# xspi_v4.net
KiCad netlist of a schematic drawn in EAGLE
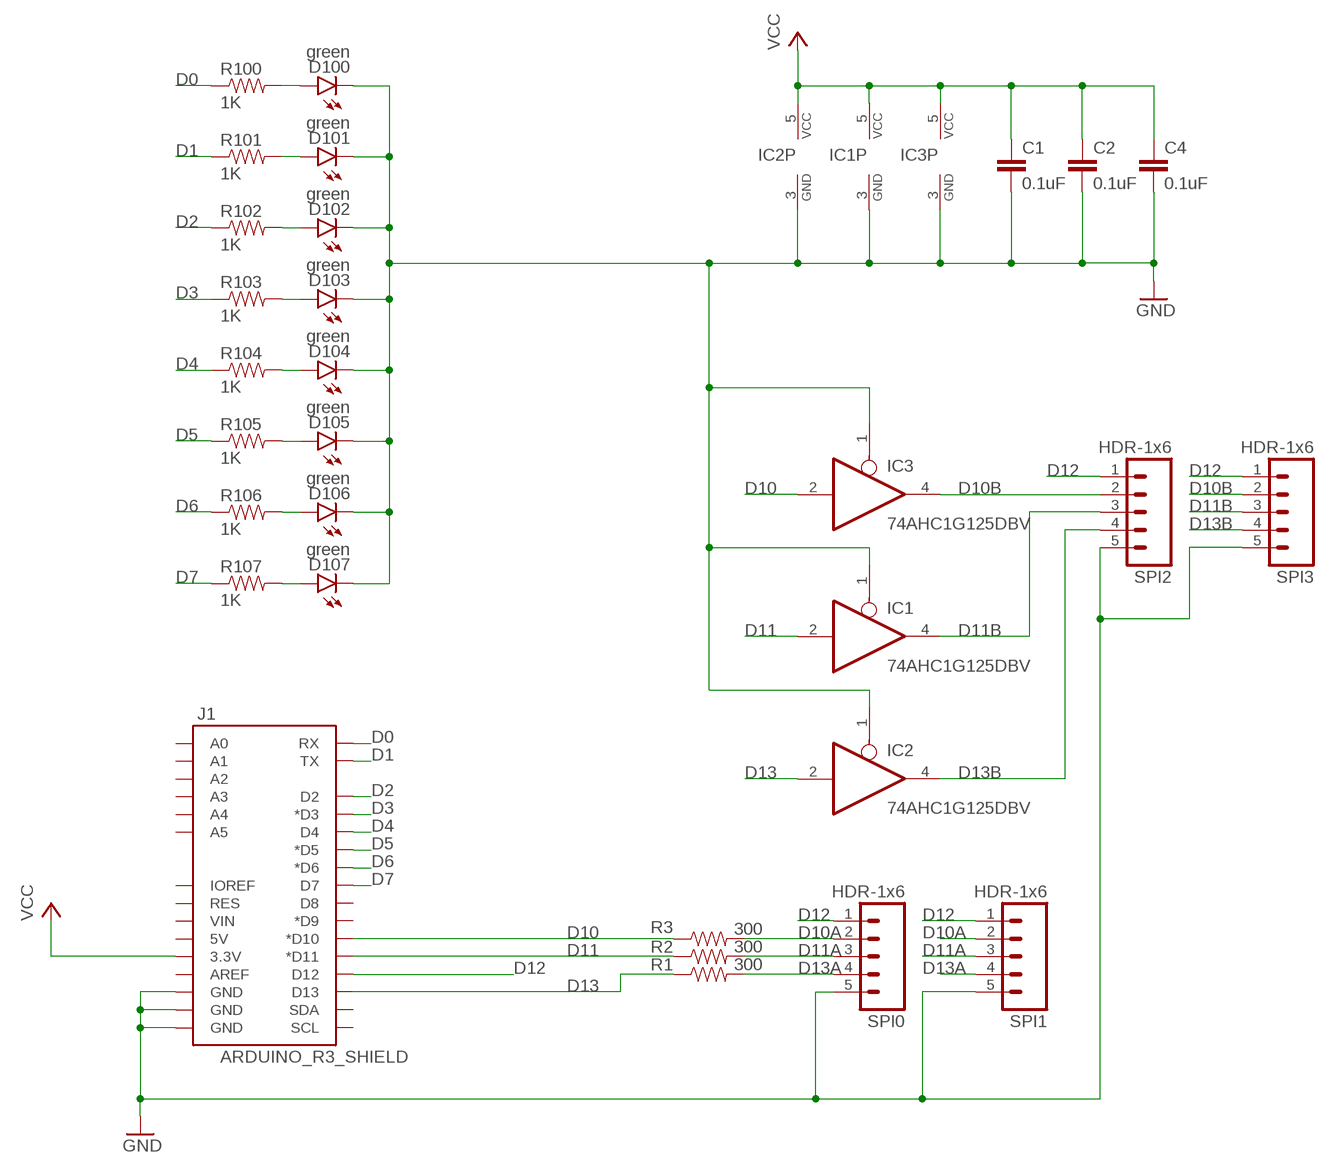
[diagram p0: schematic, sheet 1]

(export (version "E")
  (design (tool "Eeschema 10.0.6"))
  (components
    (comp (ref "C1")
      (value "0.1uF")
      (footprint "eagle-import:0805-CAP")
      (fields (field (name "PROD_ID") "0805"))
      (libsource (lib "eagle-import") (part "1.0UF-25V-+80/-20(0805){dblquote}"))
    )
    (comp (ref "C2")
      (value "0.1uF")
      (footprint "eagle-import:0805-CAP")
      (fields (field (name "PROD_ID") "0805"))
      (libsource (lib "eagle-import") (part "1.0UF-25V-+80/-20(0805){dblquote}"))
    )
    (comp (ref "C4")
      (value "0.1uF")
      (footprint "eagle-import:0805-CAP")
      (fields (field (name "PROD_ID") "0805"))
      (libsource (lib "eagle-import") (part "1.0UF-25V-+80/-20(0805){dblquote}"))
    )
    (comp (ref "D100")
      (value "green")
      (footprint "eagle-import:FKIT-LED-1206")
      (libsource (lib "eagle-import") (part "LED-FKIT-1206"))
    )
    (comp (ref "D101")
      (value "green")
      (footprint "eagle-import:FKIT-LED-1206")
      (libsource (lib "eagle-import") (part "LED-FKIT-1206"))
    )
    (comp (ref "D102")
      (value "green")
      (footprint "eagle-import:FKIT-LED-1206")
      (libsource (lib "eagle-import") (part "LED-FKIT-1206"))
    )
    (comp (ref "D103")
      (value "green")
      (footprint "eagle-import:FKIT-LED-1206")
      (libsource (lib "eagle-import") (part "LED-FKIT-1206"))
    )
    (comp (ref "D104")
      (value "green")
      (footprint "eagle-import:FKIT-LED-1206")
      (libsource (lib "eagle-import") (part "LED-FKIT-1206"))
    )
    (comp (ref "D105")
      (value "green")
      (footprint "eagle-import:FKIT-LED-1206")
      (libsource (lib "eagle-import") (part "LED-FKIT-1206"))
    )
    (comp (ref "D106")
      (value "green")
      (footprint "eagle-import:FKIT-LED-1206")
      (libsource (lib "eagle-import") (part "LED-FKIT-1206"))
    )
    (comp (ref "D107")
      (value "green")
      (footprint "eagle-import:FKIT-LED-1206")
      (libsource (lib "eagle-import") (part "LED-FKIT-1206"))
    )
    (comp (ref "IC1")
      (value "74AHC1G125DBV")
      (footprint "eagle-import:SOT23-5")
      (libsource (lib "eagle-import") (part "741G125DBVAHC"))
    )
    (comp (ref "IC2")
      (value "74AHC1G125DBV")
      (footprint "eagle-import:SOT23-5")
      (libsource (lib "eagle-import") (part "741G125DBVAHC"))
    )
    (comp (ref "IC3")
      (value "74AHC1G125DBV")
      (footprint "eagle-import:SOT23-5")
      (libsource (lib "eagle-import") (part "741G125DBVAHC"))
    )
    (comp (ref "J1")
      (value "ARDUINO_R3_SHIELD")
      (footprint "eagle-import:UNO_R3_SHIELD")
      (libsource (lib "eagle-import") (part "ARDUINO_R3_SHIELD"))
    )
    (comp (ref "R1")
      (value "300")
      (footprint "eagle-import:AXIAL-0.4")
      (libsource (lib "eagle-import") (part "RESISTORPTH-1/4W"))
    )
    (comp (ref "R2")
      (value "300")
      (footprint "eagle-import:AXIAL-0.4")
      (libsource (lib "eagle-import") (part "RESISTORPTH-1/4W"))
    )
    (comp (ref "R3")
      (value "300")
      (footprint "eagle-import:AXIAL-0.4")
      (libsource (lib "eagle-import") (part "RESISTORPTH-1/4W"))
    )
    (comp (ref "R100")
      (value "1K")
      (footprint "eagle-import:0805")
      (libsource (lib "eagle-import") (part "RESISTOR0805-RES"))
    )
    (comp (ref "R101")
      (value "1K")
      (footprint "eagle-import:0805")
      (libsource (lib "eagle-import") (part "RESISTOR0805-RES"))
    )
    (comp (ref "R102")
      (value "1K")
      (footprint "eagle-import:0805")
      (libsource (lib "eagle-import") (part "RESISTOR0805-RES"))
    )
    (comp (ref "R103")
      (value "1K")
      (footprint "eagle-import:0805")
      (libsource (lib "eagle-import") (part "RESISTOR0805-RES"))
    )
    (comp (ref "R104")
      (value "1K")
      (footprint "eagle-import:0805")
      (libsource (lib "eagle-import") (part "RESISTOR0805-RES"))
    )
    (comp (ref "R105")
      (value "1K")
      (footprint "eagle-import:0805")
      (libsource (lib "eagle-import") (part "RESISTOR0805-RES"))
    )
    (comp (ref "R106")
      (value "1K")
      (footprint "eagle-import:0805")
      (libsource (lib "eagle-import") (part "RESISTOR0805-RES"))
    )
    (comp (ref "R107")
      (value "1K")
      (footprint "eagle-import:0805")
      (libsource (lib "eagle-import") (part "RESISTOR0805-RES"))
    )
    (comp (ref "SPI0")
      (value "HDR-1x6")
      (footprint "eagle-import:1X05_LONGPADS")
      (libsource (lib "eagle-import") (part "M05PTH_LONGPADS"))
    )
    (comp (ref "SPI1")
      (value "HDR-1x6")
      (footprint "eagle-import:1X05_LONGPADS")
      (libsource (lib "eagle-import") (part "M05PTH_LONGPADS"))
    )
    (comp (ref "SPI2")
      (value "HDR-1x6")
      (footprint "eagle-import:1X05_LONGPADS")
      (libsource (lib "eagle-import") (part "M05PTH_LONGPADS"))
    )
    (comp (ref "SPI3")
      (value "HDR-1x6")
      (footprint "eagle-import:1X05_LONGPADS")
      (libsource (lib "eagle-import") (part "M05PTH_LONGPADS"))
    )
  )
  (nets
    (net (code "1") (name "/D0") (class "Default")
      (node (ref "J1") (pin "RX") (pinfunction "RX_RX") (pintype "bidirectional"))
      (node (ref "R100") (pin "1") (pinfunction "1_1") (pintype "passive"))
    )
    (net (code "2") (name "/D1") (class "Default")
      (node (ref "J1") (pin "TX") (pinfunction "TX_TX") (pintype "bidirectional"))
      (node (ref "R101") (pin "1") (pinfunction "1_1") (pintype "passive"))
    )
    (net (code "3") (name "/D2") (class "Default")
      (node (ref "J1") (pin "D2") (pinfunction "D2_D2") (pintype "bidirectional"))
      (node (ref "R102") (pin "1") (pinfunction "1_1") (pintype "passive"))
    )
    (net (code "4") (name "/D3") (class "Default")
      (node (ref "J1") (pin "D3") (pinfunction "*D3_D3") (pintype "bidirectional"))
      (node (ref "R103") (pin "1") (pinfunction "1_1") (pintype "passive"))
    )
    (net (code "5") (name "/D4") (class "Default")
      (node (ref "J1") (pin "D4") (pinfunction "D4_D4") (pintype "bidirectional"))
      (node (ref "R104") (pin "1") (pinfunction "1_1") (pintype "passive"))
    )
    (net (code "6") (name "/D5") (class "Default")
      (node (ref "J1") (pin "D5") (pinfunction "*D5_D5") (pintype "bidirectional"))
      (node (ref "R105") (pin "1") (pinfunction "1_1") (pintype "passive"))
    )
    (net (code "7") (name "/D6") (class "Default")
      (node (ref "J1") (pin "D6") (pinfunction "*D6_D6") (pintype "bidirectional"))
      (node (ref "R106") (pin "1") (pinfunction "1_1") (pintype "passive"))
    )
    (net (code "8") (name "/D7") (class "Default")
      (node (ref "J1") (pin "D7") (pinfunction "D7_D7") (pintype "bidirectional"))
      (node (ref "R107") (pin "1") (pinfunction "1_1") (pintype "passive"))
    )
    (net (code "9") (name "/D10") (class "Default")
      (node (ref "IC3") (pin "2") (pinfunction "I_2") (pintype "input"))
      (node (ref "J1") (pin "D10") (pinfunction "*D10_D10") (pintype "bidirectional"))
      (node (ref "R3") (pin "P$1") (pinfunction "1_P$1") (pintype "passive"))
    )
    (net (code "10") (name "/D10A") (class "Default")
      (node (ref "R3") (pin "P$2") (pinfunction "2_P$2") (pintype "passive"))
      (node (ref "SPI0") (pin "2") (pinfunction "2_2") (pintype "passive"))
      (node (ref "SPI1") (pin "2") (pinfunction "2_2") (pintype "passive"))
    )
    (net (code "11") (name "/D10B") (class "Default")
      (node (ref "IC3") (pin "4") (pinfunction "O_4") (pintype "tri_state"))
      (node (ref "SPI2") (pin "2") (pinfunction "2_2") (pintype "passive"))
      (node (ref "SPI3") (pin "2") (pinfunction "2_2") (pintype "passive"))
    )
    (net (code "12") (name "/D11") (class "Default")
      (node (ref "IC1") (pin "2") (pinfunction "I_2") (pintype "input"))
      (node (ref "J1") (pin "D11") (pinfunction "*D11_D11") (pintype "bidirectional"))
      (node (ref "R2") (pin "P$1") (pinfunction "1_P$1") (pintype "passive"))
    )
    (net (code "13") (name "/D11A") (class "Default")
      (node (ref "R2") (pin "P$2") (pinfunction "2_P$2") (pintype "passive"))
      (node (ref "SPI0") (pin "3") (pinfunction "3_3") (pintype "passive"))
      (node (ref "SPI1") (pin "3") (pinfunction "3_3") (pintype "passive"))
    )
    (net (code "14") (name "/D11B") (class "Default")
      (node (ref "IC1") (pin "4") (pinfunction "O_4") (pintype "tri_state"))
      (node (ref "SPI2") (pin "3") (pinfunction "3_3") (pintype "passive"))
      (node (ref "SPI3") (pin "3") (pinfunction "3_3") (pintype "passive"))
    )
    (net (code "15") (name "/D12") (class "Default")
      (node (ref "J1") (pin "D12") (pinfunction "D12_D12") (pintype "bidirectional"))
      (node (ref "SPI0") (pin "1") (pinfunction "1_1") (pintype "passive"))
      (node (ref "SPI1") (pin "1") (pinfunction "1_1") (pintype "passive"))
      (node (ref "SPI2") (pin "1") (pinfunction "1_1") (pintype "passive"))
      (node (ref "SPI3") (pin "1") (pinfunction "1_1") (pintype "passive"))
    )
    (net (code "16") (name "/D13") (class "Default")
      (node (ref "IC2") (pin "2") (pinfunction "I_2") (pintype "input"))
      (node (ref "J1") (pin "D13") (pinfunction "D13_D13") (pintype "bidirectional"))
      (node (ref "R1") (pin "P$1") (pinfunction "1_P$1") (pintype "passive"))
    )
    (net (code "17") (name "/D13A") (class "Default")
      (node (ref "R1") (pin "P$2") (pinfunction "2_P$2") (pintype "passive"))
      (node (ref "SPI0") (pin "4") (pinfunction "4_4") (pintype "passive"))
      (node (ref "SPI1") (pin "4") (pinfunction "4_4") (pintype "passive"))
    )
    (net (code "18") (name "/D13B") (class "Default")
      (node (ref "IC2") (pin "4") (pinfunction "O_4") (pintype "tri_state"))
      (node (ref "SPI2") (pin "4") (pinfunction "4_4") (pintype "passive"))
      (node (ref "SPI3") (pin "4") (pinfunction "4_4") (pintype "passive"))
    )
    (net (code "19") (name "GND") (class "Default")
      (node (ref "C1") (pin "2") (pinfunction "2_2") (pintype "passive"))
      (node (ref "C2") (pin "2") (pinfunction "2_2") (pintype "passive"))
      (node (ref "C4") (pin "2") (pinfunction "2_2") (pintype "passive"))
      (node (ref "D100") (pin "C") (pinfunction "C_C") (pintype "passive"))
      (node (ref "D101") (pin "C") (pinfunction "C_C") (pintype "passive"))
      (node (ref "D102") (pin "C") (pinfunction "C_C") (pintype "passive"))
      (node (ref "D103") (pin "C") (pinfunction "C_C") (pintype "passive"))
      (node (ref "D104") (pin "C") (pinfunction "C_C") (pintype "passive"))
      (node (ref "D105") (pin "C") (pinfunction "C_C") (pintype "passive"))
      (node (ref "D106") (pin "C") (pinfunction "C_C") (pintype "passive"))
      (node (ref "D107") (pin "C") (pinfunction "C_C") (pintype "passive"))
      (node (ref "IC1") (pin "1") (pinfunction "OE_1") (pintype "input"))
      (node (ref "IC1") (pin "3") (pinfunction "GND_3") (pintype "power_in"))
      (node (ref "IC2") (pin "1") (pinfunction "OE_1") (pintype "input"))
      (node (ref "IC2") (pin "3") (pinfunction "GND_3") (pintype "power_in"))
      (node (ref "IC3") (pin "1") (pinfunction "OE_1") (pintype "input"))
      (node (ref "IC3") (pin "3") (pinfunction "GND_3") (pintype "power_in"))
      (node (ref "J1") (pin "GND@0") (pinfunction "GND_GND@0") (pintype "bidirectional"))
      (node (ref "J1") (pin "GND@1") (pinfunction "GND_GND@1") (pintype "bidirectional"))
      (node (ref "J1") (pin "GND@2") (pinfunction "GND_GND@2") (pintype "bidirectional"))
      (node (ref "SPI0") (pin "5") (pinfunction "5_5") (pintype "passive"))
      (node (ref "SPI1") (pin "5") (pinfunction "5_5") (pintype "passive"))
      (node (ref "SPI2") (pin "5") (pinfunction "5_5") (pintype "passive"))
      (node (ref "SPI3") (pin "5") (pinfunction "5_5") (pintype "passive"))
    )
    (net (code "20") (name "Net-(D100-PadA)") (class "Default")
      (node (ref "D100") (pin "A") (pinfunction "A_A") (pintype "passive"))
      (node (ref "R100") (pin "2") (pinfunction "2_2") (pintype "passive"))
    )
    (net (code "21") (name "Net-(D101-PadA)") (class "Default")
      (node (ref "D101") (pin "A") (pinfunction "A_A") (pintype "passive"))
      (node (ref "R101") (pin "2") (pinfunction "2_2") (pintype "passive"))
    )
    (net (code "22") (name "Net-(D102-PadA)") (class "Default")
      (node (ref "D102") (pin "A") (pinfunction "A_A") (pintype "passive"))
      (node (ref "R102") (pin "2") (pinfunction "2_2") (pintype "passive"))
    )
    (net (code "23") (name "Net-(D103-PadA)") (class "Default")
      (node (ref "D103") (pin "A") (pinfunction "A_A") (pintype "passive"))
      (node (ref "R103") (pin "2") (pinfunction "2_2") (pintype "passive"))
    )
    (net (code "24") (name "Net-(D104-PadA)") (class "Default")
      (node (ref "D104") (pin "A") (pinfunction "A_A") (pintype "passive"))
      (node (ref "R104") (pin "2") (pinfunction "2_2") (pintype "passive"))
    )
    (net (code "25") (name "Net-(D105-PadA)") (class "Default")
      (node (ref "D105") (pin "A") (pinfunction "A_A") (pintype "passive"))
      (node (ref "R105") (pin "2") (pinfunction "2_2") (pintype "passive"))
    )
    (net (code "26") (name "Net-(D106-PadA)") (class "Default")
      (node (ref "D106") (pin "A") (pinfunction "A_A") (pintype "passive"))
      (node (ref "R106") (pin "2") (pinfunction "2_2") (pintype "passive"))
    )
    (net (code "27") (name "Net-(D107-PadA)") (class "Default")
      (node (ref "D107") (pin "A") (pinfunction "A_A") (pintype "passive"))
      (node (ref "R107") (pin "2") (pinfunction "2_2") (pintype "passive"))
    )
    (net (code "28") (name "VCC") (class "Default")
      (node (ref "C1") (pin "1") (pinfunction "1_1") (pintype "passive"))
      (node (ref "C2") (pin "1") (pinfunction "1_1") (pintype "passive"))
      (node (ref "C4") (pin "1") (pinfunction "1_1") (pintype "passive"))
      (node (ref "IC1") (pin "5") (pinfunction "VCC_5") (pintype "power_in"))
      (node (ref "IC2") (pin "5") (pinfunction "VCC_5") (pintype "power_in"))
      (node (ref "IC3") (pin "5") (pinfunction "VCC_5") (pintype "power_in"))
      (node (ref "J1") (pin "3.3V") (pinfunction "3.3V_3.3V") (pintype "bidirectional"))
    )
    (net (code "29") (name "unconnected-(J1-*D9-PadD9)") (class "Default")
      (node (ref "J1") (pin "D9") (pinfunction "*D9_D9") (pintype "bidirectional"))
    )
    (net (code "30") (name "unconnected-(J1-Pad5V)") (class "Default")
      (node (ref "J1") (pin "5V") (pinfunction "5V_5V") (pintype "bidirectional"))
    )
    (net (code "31") (name "unconnected-(J1-PadA0)") (class "Default")
      (node (ref "J1") (pin "A0") (pinfunction "A0_A0") (pintype "bidirectional"))
    )
    (net (code "32") (name "unconnected-(J1-PadA1)") (class "Default")
      (node (ref "J1") (pin "A1") (pinfunction "A1_A1") (pintype "bidirectional"))
    )
    (net (code "33") (name "unconnected-(J1-PadA2)") (class "Default")
      (node (ref "J1") (pin "A2") (pinfunction "A2_A2") (pintype "bidirectional"))
    )
    (net (code "34") (name "unconnected-(J1-PadA3)") (class "Default")
      (node (ref "J1") (pin "A3") (pinfunction "A3_A3") (pintype "bidirectional"))
    )
    (net (code "35") (name "unconnected-(J1-PadA4)") (class "Default")
      (node (ref "J1") (pin "A4") (pinfunction "A4_A4") (pintype "bidirectional"))
    )
    (net (code "36") (name "unconnected-(J1-PadA5)") (class "Default")
      (node (ref "J1") (pin "A5") (pinfunction "A5_A5") (pintype "bidirectional"))
    )
    (net (code "37") (name "unconnected-(J1-PadAREF)") (class "Default")
      (node (ref "J1") (pin "AREF") (pinfunction "AREF_AREF") (pintype "bidirectional"))
    )
    (net (code "38") (name "unconnected-(J1-PadD8)") (class "Default")
      (node (ref "J1") (pin "D8") (pinfunction "D8_D8") (pintype "bidirectional"))
    )
    (net (code "39") (name "unconnected-(J1-PadIOREF)") (class "Default")
      (node (ref "J1") (pin "IOREF") (pinfunction "IOREF_IOREF") (pintype "bidirectional"))
    )
    (net (code "40") (name "unconnected-(J1-PadRES)") (class "Default")
      (node (ref "J1") (pin "RES") (pinfunction "RES_RES") (pintype "bidirectional"))
    )
    (net (code "41") (name "unconnected-(J1-PadSCL)") (class "Default")
      (node (ref "J1") (pin "SCL") (pinfunction "SCL_SCL") (pintype "bidirectional"))
    )
    (net (code "42") (name "unconnected-(J1-PadSDA)") (class "Default")
      (node (ref "J1") (pin "SDA") (pinfunction "SDA_SDA") (pintype "bidirectional"))
    )
    (net (code "43") (name "unconnected-(J1-PadVIN)") (class "Default")
      (node (ref "J1") (pin "VIN") (pinfunction "VIN_VIN") (pintype "bidirectional"))
    )
  )
)
